# Whitespace_Daughtercard_ucontroller.net
KiCad netlist of a schematic drawn in Altium Designer
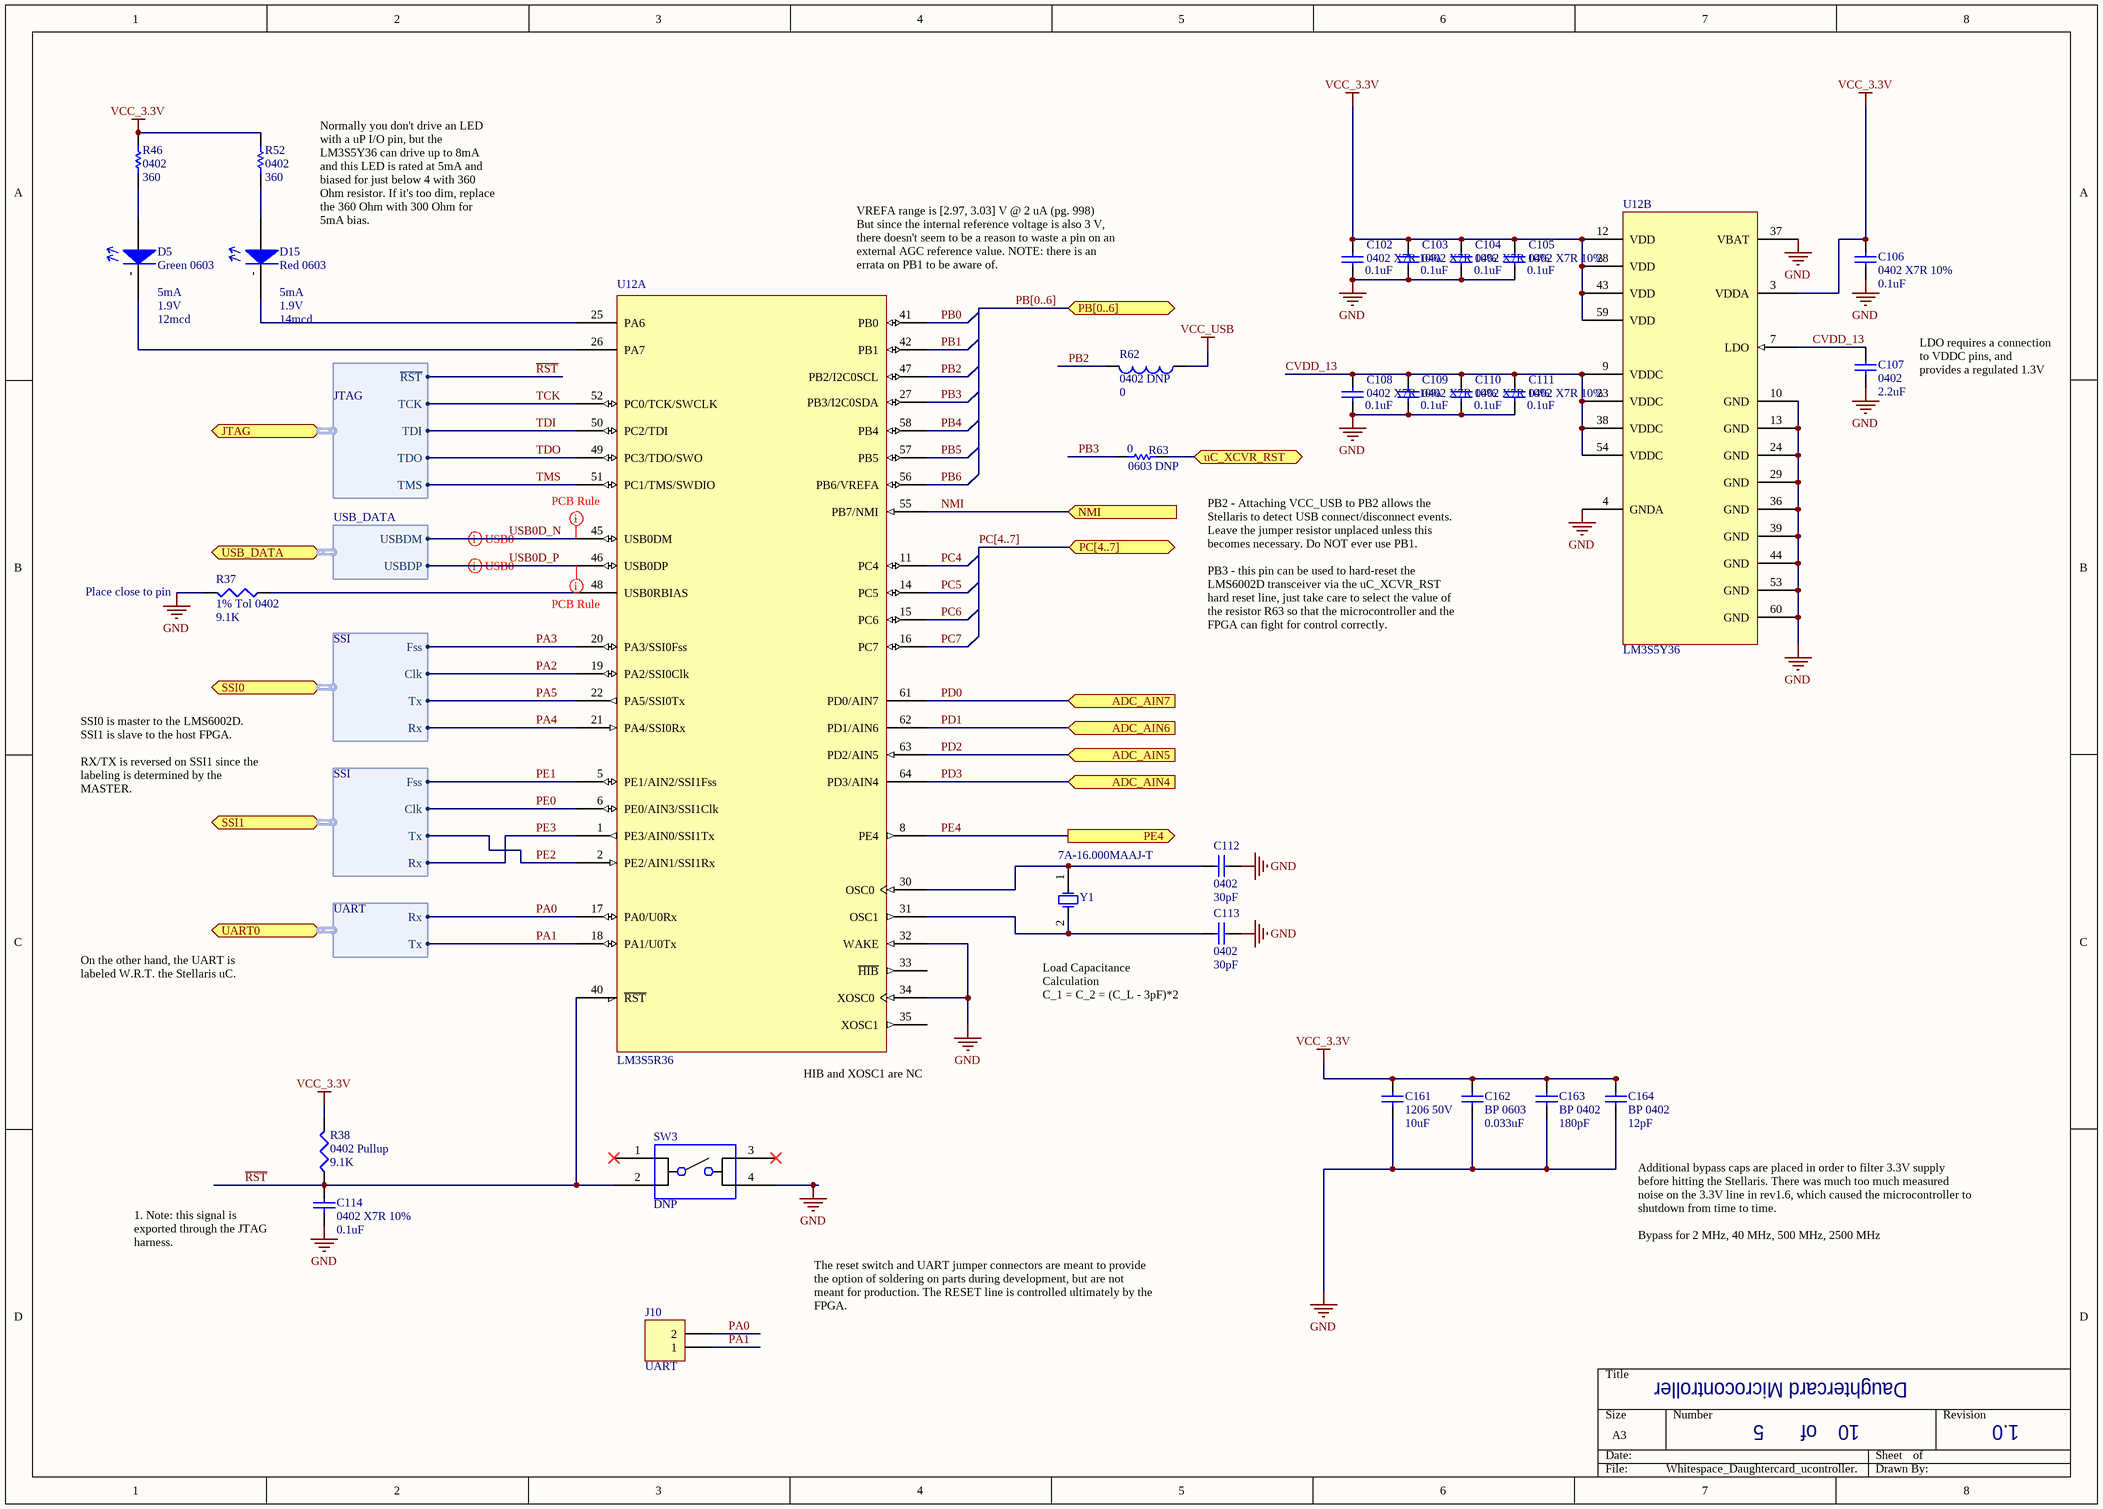
[diagram p0: Whitespace_Daughtercard_ucontroller.SchDoc]

(export (version "E")
  (design (tool "Eeschema 10.0.6"))
  (components
    (comp (ref "C102")
      (value "0402 X7R 10%")
      (footprint "0402_SMT_V3")
      (description "Capacitor")
      (fields (field (name "ALTIUM_VALUE") "0.1uF") (field (name "PUBLISHER") "Altium Limited"))
      (libsource (lib "Miscellaneous Devices") (part "Cap"))
    )
    (comp (ref "C103")
      (value "0402 X7R 10%")
      (footprint "0402_SMT_V3")
      (description "Capacitor")
      (fields (field (name "ALTIUM_VALUE") "0.1uF") (field (name "PUBLISHER") "Altium Limited"))
      (libsource (lib "Miscellaneous Devices") (part "Cap"))
    )
    (comp (ref "C104")
      (value "0402 X7R 10%")
      (footprint "0402_SMT_V3")
      (description "Capacitor")
      (fields (field (name "ALTIUM_VALUE") "0.1uF") (field (name "PUBLISHER") "Altium Limited"))
      (libsource (lib "Miscellaneous Devices") (part "Cap"))
    )
    (comp (ref "C105")
      (value "0402 X7R 10%")
      (footprint "0402_SMT_V3")
      (description "Capacitor")
      (fields (field (name "ALTIUM_VALUE") "0.1uF") (field (name "PUBLISHER") "Altium Limited"))
      (libsource (lib "Miscellaneous Devices") (part "Cap"))
    )
    (comp (ref "C106")
      (value "0402 X7R 10%")
      (footprint "0402_SMT_V3")
      (description "Capacitor")
      (fields (field (name "ALTIUM_VALUE") "0.1uF") (field (name "PUBLISHER") "Altium Limited"))
      (libsource (lib "Miscellaneous Devices") (part "Cap"))
    )
    (comp (ref "C107")
      (value "0402")
      (footprint "0402_SMT_v3")
      (description "Capacitor (Semiconductor SIM Model)")
      (fields (field (name "ALTIUM_VALUE") "2.2uF") (field (name "PUBLISHER") "Altium Limited"))
      (libsource (lib "Miscellaneous Devices") (part "Cap Semi"))
    )
    (comp (ref "C108")
      (value "0402 X7R 10%")
      (footprint "0402_SMT_V3")
      (description "Capacitor")
      (fields (field (name "ALTIUM_VALUE") "0.1uF") (field (name "PUBLISHER") "Altium Limited"))
      (libsource (lib "Miscellaneous Devices") (part "Cap"))
    )
    (comp (ref "C109")
      (value "0402 X7R 10%")
      (footprint "0402_SMT_V3")
      (description "Capacitor")
      (fields (field (name "ALTIUM_VALUE") "0.1uF") (field (name "PUBLISHER") "Altium Limited"))
      (libsource (lib "Miscellaneous Devices") (part "Cap"))
    )
    (comp (ref "C110")
      (value "0402 X7R 10%")
      (footprint "0402_SMT_V3")
      (description "Capacitor")
      (fields (field (name "ALTIUM_VALUE") "0.1uF") (field (name "PUBLISHER") "Altium Limited"))
      (libsource (lib "Miscellaneous Devices") (part "Cap"))
    )
    (comp (ref "C111")
      (value "0402 X7R 10%")
      (footprint "0402_SMT_V3")
      (description "Capacitor")
      (fields (field (name "ALTIUM_VALUE") "0.1uF") (field (name "PUBLISHER") "Altium Limited"))
      (libsource (lib "Miscellaneous Devices") (part "Cap"))
    )
    (comp (ref "C112")
      (value "0402")
      (footprint "0402_SMT_v3")
      (description "Capacitor (Semiconductor SIM Model)")
      (fields (field (name "ALTIUM_VALUE") "30pF") (field (name "PUBLISHER") "Altium Limited"))
      (libsource (lib "Miscellaneous Devices") (part "Cap Semi"))
    )
    (comp (ref "C113")
      (value "0402")
      (footprint "0402_SMT_v3")
      (description "Capacitor (Semiconductor SIM Model)")
      (fields (field (name "ALTIUM_VALUE") "30pF") (field (name "PUBLISHER") "Altium Limited"))
      (libsource (lib "Miscellaneous Devices") (part "Cap Semi"))
    )
    (comp (ref "C114")
      (value "0402 X7R 10%")
      (footprint "0402_SMT_V3")
      (description "Capacitor")
      (fields (field (name "ALTIUM_VALUE") "0.1uF") (field (name "PUBLISHER") "Altium Limited"))
      (libsource (lib "Miscellaneous Devices") (part "Cap"))
    )
    (comp (ref "C161")
      (value "1206 50V")
      (footprint "1206_SMT_v3")
      (description "Capacitor")
      (fields (field (name "ALTIUM_VALUE") "10uF") (field (name "PUBLISHER") "Altium Limited"))
      (libsource (lib "Miscellaneous Devices") (part "Cap"))
    )
    (comp (ref "C162")
      (value "BP 0603")
      (footprint "0603_SMT_v3")
      (description "Capacitor")
      (fields (field (name "ALTIUM_VALUE") "0.033uF") (field (name "PUBLISHER") "Altium Limited"))
      (libsource (lib "Miscellaneous Devices") (part "Cap"))
    )
    (comp (ref "C163")
      (value "BP 0402")
      (footprint "0402_SMT_v3")
      (description "Capacitor")
      (fields (field (name "ALTIUM_VALUE") "180pF") (field (name "PUBLISHER") "Altium Limited"))
      (libsource (lib "Miscellaneous Devices") (part "Cap"))
    )
    (comp (ref "C164")
      (value "BP 0402")
      (footprint "0402_SMT_v3")
      (description "Capacitor")
      (fields (field (name "ALTIUM_VALUE") "12pF") (field (name "PUBLISHER") "Altium Limited"))
      (libsource (lib "Miscellaneous Devices") (part "Cap"))
    )
    (comp (ref "D5")
      (value "Green 0603")
      (footprint "0603_POLAR")
      (fields
        (field (name "CURRENT") "5mA")
        (field (name "FORWARD VOLTAGE") "1.9V")
        (field (name "LUMINOSITY") "12mcd")
      )
      (libsource (lib "RNG_Parts") (part "LED"))
    )
    (comp (ref "D15")
      (value "Red 0603")
      (footprint "0603_POLAR")
      (fields
        (field (name "CURRENT") "5mA")
        (field (name "FORWARD VOLTAGE DROP") "1.9V")
        (field (name "LUMINOSITY") "14mcd")
      )
      (libsource (lib "RNG_Parts") (part "LED"))
    )
    (comp (ref "J10")
      (value "UART")
      (footprint "HDR1X2")
      (description "Header, 2-Pin")
      (fields (field (name "PUBLISHER") "Altium Limited"))
      (libsource (lib "Miscellaneous Connectors") (part "Header 2"))
    )
    (comp (ref "R37")
      (value "1% Tol 0402")
      (footprint "0402_SMT_v3")
      (description "Resistor")
      (fields (field (name "ALTIUM_VALUE") "9.1K") (field (name "PUBLISHER") "Altium Limited"))
      (libsource (lib "Miscellaneous Devices") (part "Res3"))
    )
    (comp (ref "R38")
      (value "0402 Pullup")
      (footprint "0402_SMT_v3")
      (description "Resistor")
      (fields (field (name "ALTIUM_VALUE") "9.1K") (field (name "PUBLISHER") "Altium Limited"))
      (libsource (lib "Miscellaneous Devices") (part "Res3"))
    )
    (comp (ref "R46")
      (value "0402")
      (footprint "0402_SMT_v3")
      (description "Semiconductor Resistor")
      (fields (field (name "ALTIUM_VALUE") "360") (field (name "PUBLISHER") "Altium Limited"))
      (libsource (lib "Miscellaneous Devices") (part "Res Semi"))
    )
    (comp (ref "R52")
      (value "0402")
      (footprint "0402_SMT_v3")
      (description "Semiconductor Resistor")
      (fields (field (name "ALTIUM_VALUE") "360") (field (name "PUBLISHER") "Altium Limited"))
      (libsource (lib "Miscellaneous Devices") (part "Res Semi"))
    )
    (comp (ref "R62")
      (value "0402 DNP")
      (footprint "0402_SMT_V3")
      (description "Inductor")
      (fields (field (name "ALTIUM_VALUE") "0") (field (name "PUBLISHER") "Altium Limited"))
      (libsource (lib "Miscellaneous Devices") (part "Inductor"))
    )
    (comp (ref "R63")
      (value "0603 DNP")
      (footprint "0603_SMT_v3")
      (description "Semiconductor Resistor")
      (fields (field (name "ALTIUM_VALUE") "0") (field (name "PUBLISHER") "Altium Limited"))
      (libsource (lib "Miscellaneous Devices") (part "Res Semi"))
    )
    (comp (ref "SW3")
      (value "DNP")
      (footprint "PUSHBUTTON_SW2_SMT")
      (description "Pushbutton Switch - Long Button")
      (libsource (lib "RNG_Parts") (part "SMT-PUSHBUTTON-SW"))
    )
    (comp (ref "U12")
      (value "LM3S5Y36")
      (footprint "PQFP-64-TI_Stellaris")
      (description "TI Stellaris LM3S5Y36 Microcontroller")
      (libsource (lib "RNG_Parts") (part "LM3S5Y36"))
    )
    (comp (ref "Y1")
      (value "7A-16.000MAAJ-T")
      (footprint "XTAL_SMT_5_3-2_v2")
      (description "Crystal Oscillator")
      (fields (field (name "PUBLISHER") "Altium Limited"))
      (libsource (lib "Miscellaneous Devices") (part "XTAL"))
    )
  )
  (nets
    (net (code "5") (name "/CVDD_13") (class "Default")
      (node (ref "C107") (pin "1") (pinfunction "1_1") (pintype "passive"))
      (node (ref "C108") (pin "2") (pinfunction "2_2") (pintype "passive"))
      (node (ref "C109") (pin "2") (pinfunction "2_2") (pintype "passive"))
      (node (ref "C110") (pin "2") (pinfunction "2_2") (pintype "passive"))
      (node (ref "C111") (pin "2") (pinfunction "2_2") (pintype "passive"))
      (node (ref "U12") (pin "23") (pinfunction "VDDC_23") (pintype "power_in"))
      (node (ref "U12") (pin "38") (pinfunction "VDDC_38") (pintype "power_in"))
      (node (ref "U12") (pin "54") (pinfunction "VDDC_54") (pintype "power_in"))
      (node (ref "U12") (pin "7") (pinfunction "LDO_7") (pintype "input"))
      (node (ref "U12") (pin "9") (pinfunction "VDDC_9") (pintype "power_in"))
    )
    (net (code "6") (name "/NMI") (class "Default")
      (node (ref "U12") (pin "55") (pinfunction "PB7/NMI_55") (pintype "input"))
    )
    (net (code "7") (name "/PA0") (class "Default")
      (node (ref "J10") (pin "2") (pinfunction "2_2") (pintype "passive"))
      (node (ref "U12") (pin "17") (pinfunction "PA0/U0Rx_17") (pintype "bidirectional"))
    )
    (net (code "8") (name "/PA1") (class "Default")
      (node (ref "J10") (pin "1") (pinfunction "1_1") (pintype "passive"))
      (node (ref "U12") (pin "18") (pinfunction "PA1/U0Tx_18") (pintype "bidirectional"))
    )
    (net (code "9") (name "/PA2") (class "Default")
      (node (ref "U12") (pin "19") (pinfunction "PA2/SSI0Clk_19") (pintype "bidirectional"))
    )
    (net (code "10") (name "/PA3") (class "Default")
      (node (ref "U12") (pin "20") (pinfunction "PA3/SSI0Fss_20") (pintype "bidirectional"))
    )
    (net (code "11") (name "/PA4") (class "Default")
      (node (ref "U12") (pin "21") (pinfunction "PA4/SSI0Rx_21") (pintype "input"))
    )
    (net (code "12") (name "/PA5") (class "Default")
      (node (ref "U12") (pin "22") (pinfunction "PA5/SSI0Tx_22") (pintype "output"))
    )
    (net (code "13") (name "/PB0") (class "Default")
      (node (ref "U12") (pin "41") (pinfunction "PB0_41") (pintype "bidirectional"))
    )
    (net (code "14") (name "/PB1") (class "Default")
      (node (ref "U12") (pin "42") (pinfunction "PB1_42") (pintype "bidirectional"))
    )
    (net (code "15") (name "/PB2") (class "Default")
      (node (ref "R62") (pin "2") (pinfunction "2_2") (pintype "passive"))
      (node (ref "U12") (pin "47") (pinfunction "PB2/I2C0SCL_47") (pintype "bidirectional"))
    )
    (net (code "16") (name "/PB3") (class "Default")
      (node (ref "R63") (pin "2") (pinfunction "2_2") (pintype "passive"))
      (node (ref "U12") (pin "27") (pinfunction "PB3/I2C0SDA_27") (pintype "bidirectional"))
    )
    (net (code "17") (name "/PB4") (class "Default")
      (node (ref "U12") (pin "58") (pinfunction "PB4_58") (pintype "bidirectional"))
    )
    (net (code "18") (name "/PB5") (class "Default")
      (node (ref "U12") (pin "57") (pinfunction "PB5_57") (pintype "bidirectional"))
    )
    (net (code "19") (name "/PB6") (class "Default")
      (node (ref "U12") (pin "56") (pinfunction "PB6/VREFA_56") (pintype "bidirectional"))
    )
    (net (code "21") (name "/PC4") (class "Default")
      (node (ref "U12") (pin "11") (pinfunction "PC4_11") (pintype "bidirectional"))
    )
    (net (code "22") (name "/PC5") (class "Default")
      (node (ref "U12") (pin "14") (pinfunction "PC5_14") (pintype "bidirectional"))
    )
    (net (code "23") (name "/PC6") (class "Default")
      (node (ref "U12") (pin "15") (pinfunction "PC6_15") (pintype "bidirectional"))
    )
    (net (code "24") (name "/PC7") (class "Default")
      (node (ref "U12") (pin "16") (pinfunction "PC7_16") (pintype "bidirectional"))
    )
    (net (code "26") (name "/PD0") (class "Default")
      (node (ref "U12") (pin "61") (pinfunction "PD0/AIN7_61") (pintype "passive"))
    )
    (net (code "27") (name "/PD1") (class "Default")
      (node (ref "U12") (pin "62") (pinfunction "PD1/AIN6_62") (pintype "passive"))
    )
    (net (code "28") (name "/PD2") (class "Default")
      (node (ref "U12") (pin "63") (pinfunction "PD2/AIN5_63") (pintype "input"))
    )
    (net (code "29") (name "/PD3") (class "Default")
      (node (ref "U12") (pin "64") (pinfunction "PD3/AIN4_64") (pintype "passive"))
    )
    (net (code "30") (name "/PE0") (class "Default")
      (node (ref "U12") (pin "6") (pinfunction "PE0/AIN3/SSI1Clk_6") (pintype "bidirectional"))
    )
    (net (code "31") (name "/PE1") (class "Default")
      (node (ref "U12") (pin "5") (pinfunction "PE1/AIN2/SSI1Fss_5") (pintype "bidirectional"))
    )
    (net (code "32") (name "/PE2") (class "Default")
      (node (ref "U12") (pin "2") (pinfunction "PE2/AIN1/SSI1Rx_2") (pintype "input"))
    )
    (net (code "33") (name "/PE3") (class "Default")
      (node (ref "U12") (pin "1") (pinfunction "PE3/AIN0/SSI1Tx_1") (pintype "output"))
    )
    (net (code "34") (name "/PE4") (class "Default")
      (node (ref "U12") (pin "8") (pinfunction "PE4_8") (pintype "output"))
    )
    (net (code "35") (name "/RST") (class "Default")
      (node (ref "C114") (pin "1") (pinfunction "1_1") (pintype "passive"))
      (node (ref "R38") (pin "1") (pinfunction "1_1") (pintype "passive"))
      (node (ref "SW3") (pin "2") (pinfunction "2_2") (pintype "passive"))
      (node (ref "U12") (pin "40") (pinfunction "RST_40") (pintype "tri_state"))
    )
    (net (code "36") (name "/TCK") (class "Default")
      (node (ref "U12") (pin "52") (pinfunction "PC0/TCK/SWCLK_52") (pintype "bidirectional"))
    )
    (net (code "37") (name "/TDI") (class "Default")
      (node (ref "U12") (pin "50") (pinfunction "PC2/TDI_50") (pintype "bidirectional"))
    )
    (net (code "38") (name "/TDO") (class "Default")
      (node (ref "U12") (pin "49") (pinfunction "PC3/TDO/SWO_49") (pintype "bidirectional"))
    )
    (net (code "39") (name "/TMS") (class "Default")
      (node (ref "U12") (pin "51") (pinfunction "PC1/TMS/SWDIO_51") (pintype "bidirectional"))
    )
    (net (code "40") (name "/USB0D_N") (class "Default")
      (node (ref "U12") (pin "45") (pinfunction "USB0DM_45") (pintype "bidirectional"))
    )
    (net (code "41") (name "/USB0D_P") (class "Default")
      (node (ref "U12") (pin "46") (pinfunction "USB0DP_46") (pintype "bidirectional"))
    )
    (net (code "42") (name "/uC_XCVR_RST") (class "Default")
      (node (ref "R63") (pin "1") (pinfunction "1_1") (pintype "passive"))
    )
    (net (code "47") (name "GND") (class "Default")
      (node (ref "C102") (pin "1") (pinfunction "1_1") (pintype "passive"))
      (node (ref "C103") (pin "1") (pinfunction "1_1") (pintype "passive"))
      (node (ref "C104") (pin "1") (pinfunction "1_1") (pintype "passive"))
      (node (ref "C105") (pin "1") (pinfunction "1_1") (pintype "passive"))
      (node (ref "C106") (pin "2") (pinfunction "2_2") (pintype "passive"))
      (node (ref "C107") (pin "2") (pinfunction "2_2") (pintype "passive"))
      (node (ref "C108") (pin "1") (pinfunction "1_1") (pintype "passive"))
      (node (ref "C109") (pin "1") (pinfunction "1_1") (pintype "passive"))
      (node (ref "C110") (pin "1") (pinfunction "1_1") (pintype "passive"))
      (node (ref "C111") (pin "1") (pinfunction "1_1") (pintype "passive"))
      (node (ref "C112") (pin "2") (pinfunction "2_2") (pintype "passive"))
      (node (ref "C113") (pin "2") (pinfunction "2_2") (pintype "passive"))
      (node (ref "C114") (pin "2") (pinfunction "2_2") (pintype "passive"))
      (node (ref "C161") (pin "1") (pinfunction "1_1") (pintype "passive"))
      (node (ref "C162") (pin "2") (pinfunction "2_2") (pintype "passive"))
      (node (ref "C163") (pin "2") (pinfunction "2_2") (pintype "passive"))
      (node (ref "C164") (pin "2") (pinfunction "2_2") (pintype "passive"))
      (node (ref "R37") (pin "2") (pinfunction "2_2") (pintype "passive"))
      (node (ref "SW3") (pin "4") (pinfunction "4_4") (pintype "passive"))
      (node (ref "U12") (pin "10") (pinfunction "GND_10") (pintype "power_in"))
      (node (ref "U12") (pin "13") (pinfunction "GND_13") (pintype "power_in"))
      (node (ref "U12") (pin "24") (pinfunction "GND_24") (pintype "power_in"))
      (node (ref "U12") (pin "29") (pinfunction "GND_29") (pintype "power_in"))
      (node (ref "U12") (pin "32") (pinfunction "WAKE_32") (pintype "input"))
      (node (ref "U12") (pin "34") (pinfunction "XOSC0_34") (pintype "input"))
      (node (ref "U12") (pin "36") (pinfunction "GND_36") (pintype "power_in"))
      (node (ref "U12") (pin "37") (pinfunction "VBAT_37") (pintype "power_in"))
      (node (ref "U12") (pin "39") (pinfunction "GND_39") (pintype "power_in"))
      (node (ref "U12") (pin "4") (pinfunction "GNDA_4") (pintype "power_in"))
      (node (ref "U12") (pin "44") (pinfunction "GND_44") (pintype "power_in"))
      (node (ref "U12") (pin "53") (pinfunction "GND_53") (pintype "power_in"))
      (node (ref "U12") (pin "60") (pinfunction "GND_60") (pintype "power_in"))
    )
    (net (code "48") (name "Net-(D5-Anode)") (class "Default")
      (node (ref "D5") (pin "+") (pinfunction "Anode_+") (pintype "power_in"))
      (node (ref "R46") (pin "1") (pinfunction "1_1") (pintype "passive"))
    )
    (net (code "49") (name "Net-(D5-Cathode)") (class "Default")
      (node (ref "D5") (pin "-") (pinfunction "Cathode_-") (pintype "power_in"))
      (node (ref "U12") (pin "26") (pinfunction "PA7_26") (pintype "passive"))
    )
    (net (code "50") (name "Net-(D15-Anode)") (class "Default")
      (node (ref "D15") (pin "+") (pinfunction "Anode_+") (pintype "power_in"))
      (node (ref "R52") (pin "1") (pinfunction "1_1") (pintype "passive"))
    )
    (net (code "51") (name "Net-(D15-Cathode)") (class "Default")
      (node (ref "D15") (pin "-") (pinfunction "Cathode_-") (pintype "power_in"))
      (node (ref "U12") (pin "25") (pinfunction "PA6_25") (pintype "passive"))
    )
    (net (code "52") (name "Net-(U12A-OSC0)") (class "Default")
      (node (ref "C112") (pin "1") (pinfunction "1_1") (pintype "passive"))
      (node (ref "U12") (pin "30") (pinfunction "OSC0_30") (pintype "input"))
      (node (ref "Y1") (pin "1") (pinfunction "OSC1_1") (pintype "passive"))
    )
    (net (code "53") (name "Net-(U12A-OSC1)") (class "Default")
      (node (ref "C113") (pin "1") (pinfunction "1_1") (pintype "passive"))
      (node (ref "U12") (pin "31") (pinfunction "OSC1_31") (pintype "output"))
      (node (ref "Y1") (pin "2") (pinfunction "OSC2_2") (pintype "passive"))
    )
    (net (code "54") (name "Net-(U12A-USB0RBIAS)") (class "Default")
      (node (ref "R37") (pin "1") (pinfunction "1_1") (pintype "passive"))
      (node (ref "U12") (pin "48") (pinfunction "USB0RBIAS_48") (pintype "passive"))
    )
    (net (code "55") (name "VCC_3.3V") (class "Default")
      (node (ref "C102") (pin "2") (pinfunction "2_2") (pintype "passive"))
      (node (ref "C103") (pin "2") (pinfunction "2_2") (pintype "passive"))
      (node (ref "C104") (pin "2") (pinfunction "2_2") (pintype "passive"))
      (node (ref "C105") (pin "2") (pinfunction "2_2") (pintype "passive"))
      (node (ref "C106") (pin "1") (pinfunction "1_1") (pintype "passive"))
      (node (ref "C161") (pin "2") (pinfunction "2_2") (pintype "passive"))
      (node (ref "C162") (pin "1") (pinfunction "1_1") (pintype "passive"))
      (node (ref "C163") (pin "1") (pinfunction "1_1") (pintype "passive"))
      (node (ref "C164") (pin "1") (pinfunction "1_1") (pintype "passive"))
      (node (ref "R38") (pin "2") (pinfunction "2_2") (pintype "passive"))
      (node (ref "R46") (pin "2") (pinfunction "2_2") (pintype "passive"))
      (node (ref "R52") (pin "2") (pinfunction "2_2") (pintype "passive"))
      (node (ref "U12") (pin "12") (pinfunction "VDD_12") (pintype "power_in"))
      (node (ref "U12") (pin "28") (pinfunction "VDD_28") (pintype "power_in"))
      (node (ref "U12") (pin "3") (pinfunction "VDDA_3") (pintype "power_in"))
      (node (ref "U12") (pin "43") (pinfunction "VDD_43") (pintype "power_in"))
      (node (ref "U12") (pin "59") (pinfunction "VDD_59") (pintype "power_in"))
    )
    (net (code "56") (name "VCC_USB") (class "Default")
      (node (ref "R62") (pin "1") (pinfunction "1_1") (pintype "passive"))
    )
    (net (code "57") (name "unconnected-(SW3-Pad1)") (class "Default")
      (node (ref "SW3") (pin "1") (pinfunction "1_1") (pintype "passive+no_connect"))
    )
    (net (code "58") (name "unconnected-(SW3-Pad3)") (class "Default")
      (node (ref "SW3") (pin "3") (pinfunction "3_3") (pintype "passive+no_connect"))
    )
    (net (code "59") (name "unconnected-(U12A-HIB-Pad33)") (class "Default")
      (node (ref "U12") (pin "33") (pinfunction "HIB_33") (pintype "output"))
    )
    (net (code "60") (name "unconnected-(U12A-XOSC1-Pad35)") (class "Default")
      (node (ref "U12") (pin "35") (pinfunction "XOSC1_35") (pintype "output"))
    )
  )
)
